# 6502__R8_EXP1.net
KiCad netlist of a schematic drawn in EAGLE
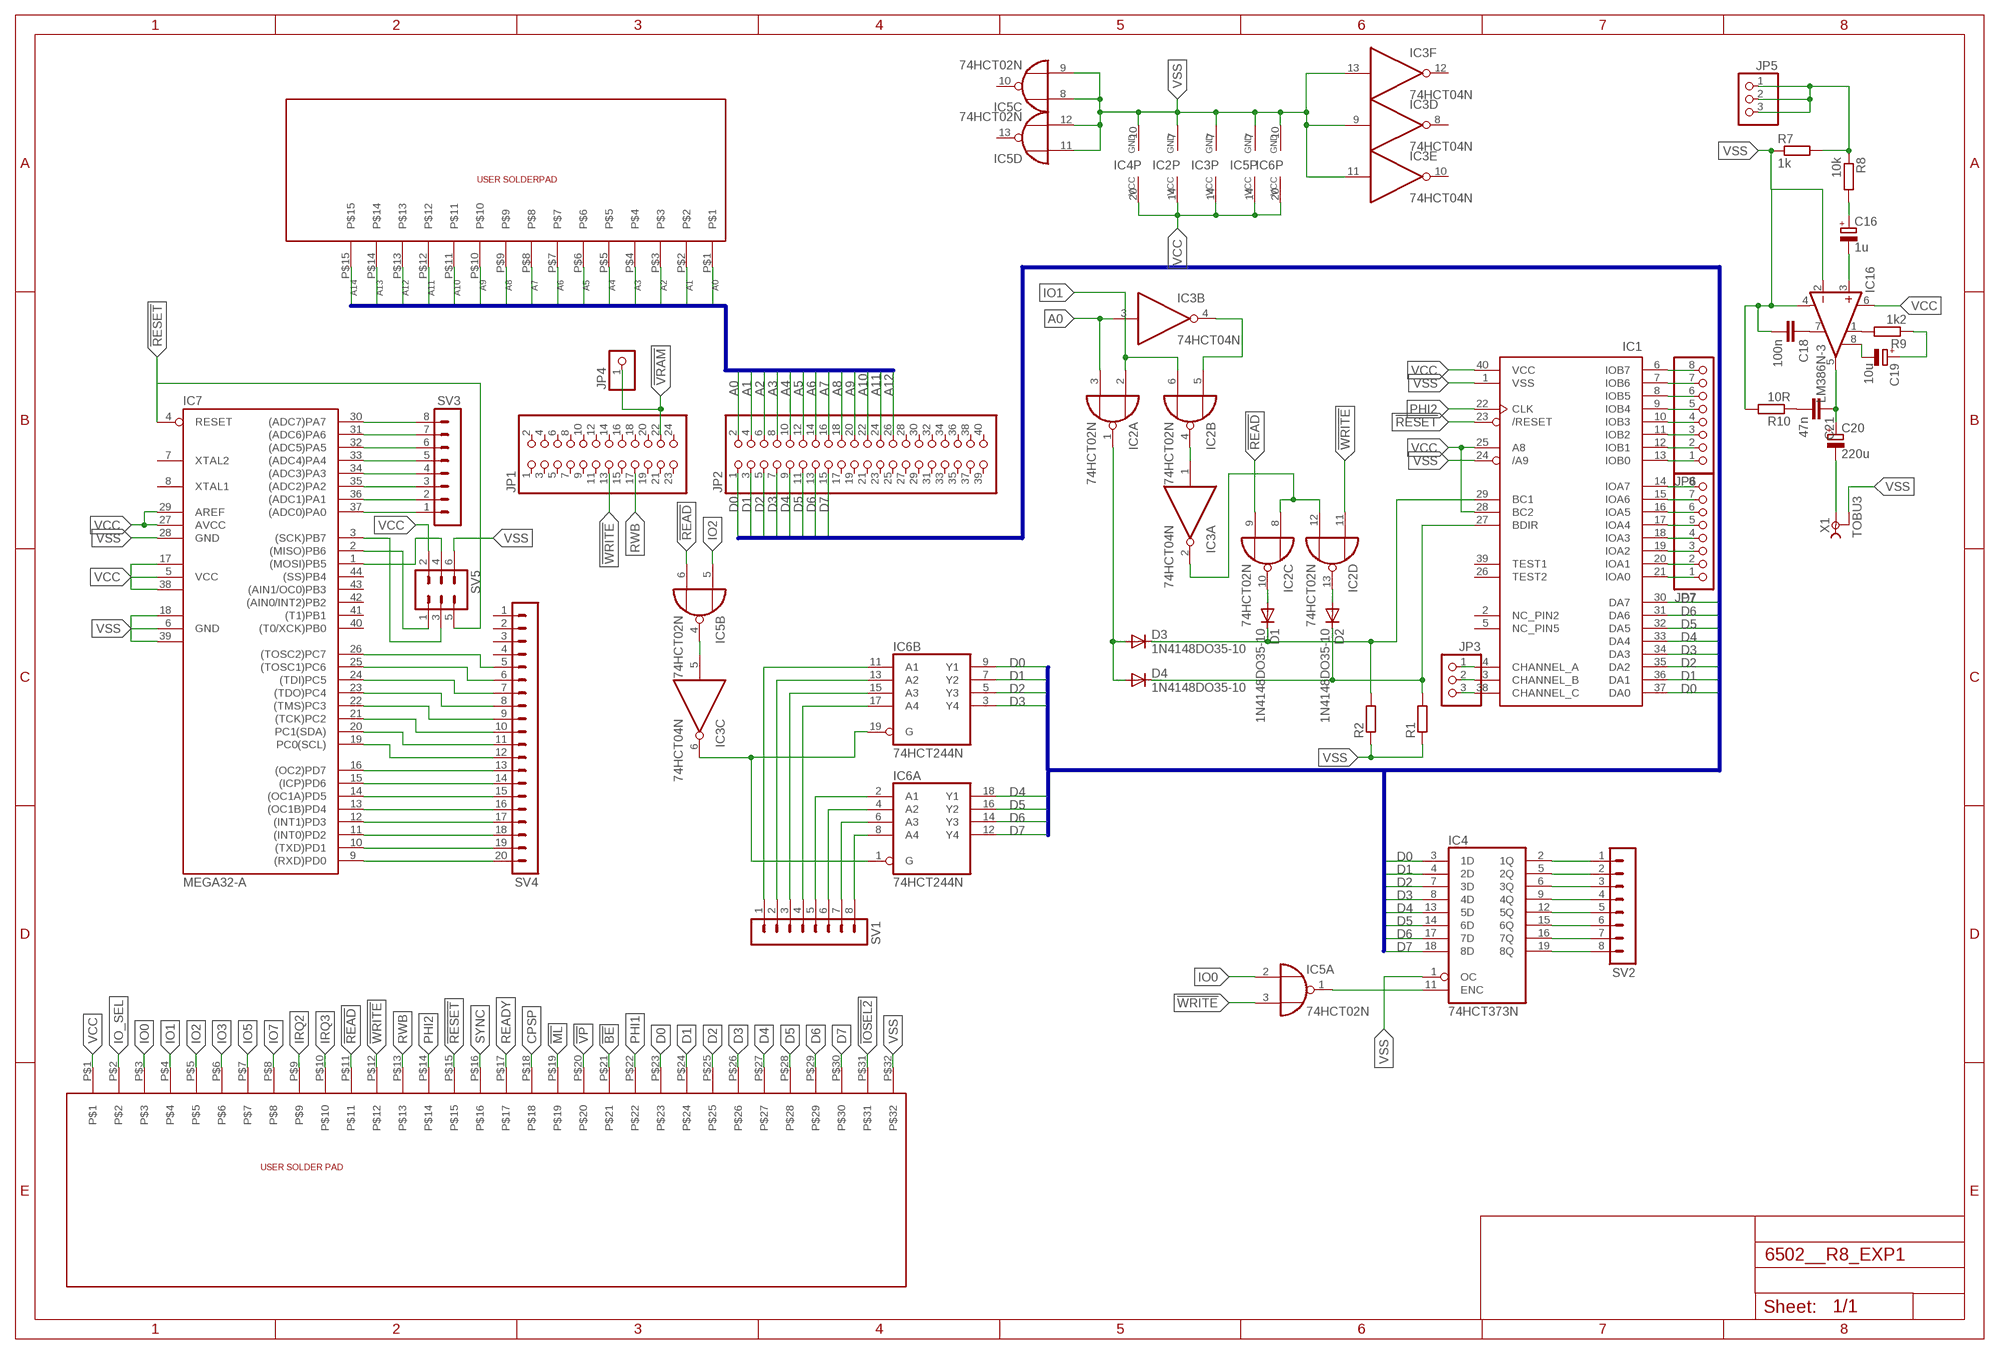
[diagram p0: schematic, sheet 1]

(export (version "E")
  (design (tool "Eeschema 10.0.6"))
  (components
    (comp (ref "C16")
      (value "1u")
      (footprint "eagle-import:E5-5")
      (libsource (lib "eagle-import") (part "CPOL-EUE5-5"))
    )
    (comp (ref "C18")
      (value "100n")
      (footprint "eagle-import:C025-030X050")
      (libsource (lib "eagle-import") (part "C-EU025-030X050"))
    )
    (comp (ref "C19")
      (value "10u")
      (footprint "eagle-import:E5-5")
      (libsource (lib "eagle-import") (part "CPOL-EUE5-5"))
    )
    (comp (ref "C20")
      (value "220u")
      (footprint "eagle-import:E5-5")
      (libsource (lib "eagle-import") (part "CPOL-EUE5-5"))
    )
    (comp (ref "C21")
      (value "47n")
      (footprint "eagle-import:C025-030X050")
      (libsource (lib "eagle-import") (part "C-EU025-030X050"))
    )
    (comp (ref "D1")
      (value "1N4148DO35-10")
      (footprint "eagle-import:DO35-10")
      (libsource (lib "eagle-import") (part "1N4148DO35-10"))
    )
    (comp (ref "D2")
      (value "1N4148DO35-10")
      (footprint "eagle-import:DO35-10")
      (libsource (lib "eagle-import") (part "1N4148DO35-10"))
    )
    (comp (ref "D3")
      (value "1N4148DO35-10")
      (footprint "eagle-import:DO35-10")
      (libsource (lib "eagle-import") (part "1N4148DO35-10"))
    )
    (comp (ref "D4")
      (value "1N4148DO35-10")
      (footprint "eagle-import:DO35-10")
      (libsource (lib "eagle-import") (part "1N4148DO35-10"))
    )
    (comp (ref "IC1")
      (value "AY-3-8910")
      (footprint "eagle-import:DIL40")
      (libsource (lib "eagle-import") (part "AY-3-8910"))
    )
    (comp (ref "IC2")
      (value "74HCT02N")
      (footprint "eagle-import:DIL14")
      (libsource (lib "eagle-import") (part "7402NHCT"))
    )
    (comp (ref "IC3")
      (value "74HCT04N")
      (footprint "eagle-import:DIL14")
      (libsource (lib "eagle-import") (part "7404NHCT"))
    )
    (comp (ref "IC4")
      (value "74HCT373N")
      (footprint "eagle-import:DIL20")
      (libsource (lib "eagle-import") (part "74373NHCT"))
    )
    (comp (ref "IC5")
      (value "74HCT02N")
      (footprint "eagle-import:DIL14")
      (libsource (lib "eagle-import") (part "7402NHCT"))
    )
    (comp (ref "IC6")
      (value "74HCT244N")
      (footprint "eagle-import:DIL20")
      (libsource (lib "eagle-import") (part "74244NHCT"))
    )
    (comp (ref "IC7")
      (value "MEGA32-A")
      (footprint "eagle-import:TQFP44")
      (fields (field (name "MPN") "ATMEGA32-16AU"))
      (libsource (lib "eagle-import") (part "MEGA32-A"))
    )
    (comp (ref "IC16")
      (value "LM386N-3")
      (footprint "eagle-import:DIL08")
      (libsource (lib "eagle-import") (part "LM386?-N3"))
    )
    (comp (ref "JP1")
      (value "PINHD-2X12")
      (footprint "eagle-import:2X12")
      (libsource (lib "eagle-import") (part "PINHD-2X12"))
    )
    (comp (ref "JP2")
      (value "PINHD-2X20")
      (footprint "eagle-import:2X20")
      (libsource (lib "eagle-import") (part "PINHD-2X20"))
    )
    (comp (ref "JP3")
      (value "PINHD-1X3")
      (footprint "eagle-import:1X03")
      (libsource (lib "eagle-import") (part "PINHD-1X3"))
    )
    (comp (ref "JP4")
      (value "PINHD-1X1")
      (footprint "eagle-import:1X01")
      (libsource (lib "eagle-import") (part "PINHD-1X1"))
    )
    (comp (ref "JP5")
      (value "PINHD-1X3")
      (footprint "eagle-import:1X03")
      (libsource (lib "eagle-import") (part "PINHD-1X3"))
    )
    (comp (ref "JP6")
      (value "PINHD-1X8")
      (footprint "eagle-import:1X08")
      (libsource (lib "eagle-import") (part "PINHD-1X8"))
    )
    (comp (ref "JP7")
      (value "PINHD-1X8")
      (footprint "eagle-import:1X08")
      (libsource (lib "eagle-import") (part "PINHD-1X8"))
    )
    (comp (ref "R1")
      (value "R-EU_0204/7")
      (footprint "eagle-import:0204_7")
      (libsource (lib "eagle-import") (part "R-EU_0204/7"))
    )
    (comp (ref "R2")
      (value "R-EU_0204/7")
      (footprint "eagle-import:0204_7")
      (libsource (lib "eagle-import") (part "R-EU_0204/7"))
    )
    (comp (ref "R7")
      (value "1k")
      (footprint "eagle-import:0207_12")
      (libsource (lib "eagle-import") (part "R-EU_0207/12"))
    )
    (comp (ref "R8")
      (value "10k")
      (footprint "eagle-import:0207_12")
      (libsource (lib "eagle-import") (part "R-EU_0207/12"))
    )
    (comp (ref "R9")
      (value "1k2")
      (footprint "eagle-import:0207_12")
      (libsource (lib "eagle-import") (part "R-EU_0207/12"))
    )
    (comp (ref "R10")
      (value "10R")
      (footprint "eagle-import:0207_12")
      (libsource (lib "eagle-import") (part "R-EU_0207/12"))
    )
    (comp (ref "SV1")
      (value "MA08-1")
      (footprint "eagle-import:MA08-1")
      (libsource (lib "eagle-import") (part "MA08-1"))
    )
    (comp (ref "SV2")
      (value "MA08-1")
      (footprint "eagle-import:MA08-1")
      (libsource (lib "eagle-import") (part "MA08-1"))
    )
    (comp (ref "SV3")
      (value "MA08-1")
      (footprint "eagle-import:MA08-1")
      (libsource (lib "eagle-import") (part "MA08-1"))
    )
    (comp (ref "SV4")
      (value "MA20-1")
      (footprint "eagle-import:MA20-1")
      (libsource (lib "eagle-import") (part "MA20-1"))
    )
    (comp (ref "SV5")
      (value "MA03-2")
      (footprint "eagle-import:MA03-2")
      (libsource (lib "eagle-import") (part "MA03-2"))
    )
    (comp (ref "U$2")
      (value "SOLDERPAD")
      (footprint "eagle-import:SOLDERPAD")
      (libsource (lib "eagle-import") (part "SOLDERPAD"))
    )
    (comp (ref "U$3")
      (value "SOLDERPAD2")
      (footprint "eagle-import:SOLDERPAD2")
      (libsource (lib "eagle-import") (part "SOLDERPAD2"))
    )
    (comp (ref "X1")
      (value "TOBU3")
      (footprint "eagle-import:TOBU3")
      (fields (field (name "MF") "FARNELL") (field (name "MPN") "TOBU 3"))
      (libsource (lib "eagle-import") (part "TOBU3"))
    )
  )
  (nets
    (net (code "1") (name "/A1") (class "Default")
      (node (ref "JP2") (pin "4") (pinfunction "4_4") (pintype "passive"))
      (node (ref "U$3") (pin "P$2") (pinfunction "P$2_P$2") (pintype "bidirectional"))
    )
    (net (code "2") (name "/A2") (class "Default")
      (node (ref "JP2") (pin "6") (pinfunction "6_6") (pintype "passive"))
      (node (ref "U$3") (pin "P$3") (pinfunction "P$3_P$3") (pintype "bidirectional"))
    )
    (net (code "3") (name "/A3") (class "Default")
      (node (ref "JP2") (pin "8") (pinfunction "8_8") (pintype "passive"))
      (node (ref "U$3") (pin "P$4") (pinfunction "P$4_P$4") (pintype "bidirectional"))
    )
    (net (code "4") (name "/A4") (class "Default")
      (node (ref "JP2") (pin "10") (pinfunction "10_10") (pintype "passive"))
      (node (ref "U$3") (pin "P$5") (pinfunction "P$5_P$5") (pintype "bidirectional"))
    )
    (net (code "5") (name "/A5") (class "Default")
      (node (ref "JP2") (pin "12") (pinfunction "12_12") (pintype "passive"))
      (node (ref "U$3") (pin "P$6") (pinfunction "P$6_P$6") (pintype "bidirectional"))
    )
    (net (code "6") (name "/A6") (class "Default")
      (node (ref "JP2") (pin "14") (pinfunction "14_14") (pintype "passive"))
      (node (ref "U$3") (pin "P$7") (pinfunction "P$7_P$7") (pintype "bidirectional"))
    )
    (net (code "7") (name "/A7") (class "Default")
      (node (ref "JP2") (pin "16") (pinfunction "16_16") (pintype "passive"))
      (node (ref "U$3") (pin "P$8") (pinfunction "P$8_P$8") (pintype "bidirectional"))
    )
    (net (code "8") (name "/A8") (class "Default")
      (node (ref "JP2") (pin "18") (pinfunction "18_18") (pintype "passive"))
      (node (ref "U$3") (pin "P$9") (pinfunction "P$9_P$9") (pintype "bidirectional"))
    )
    (net (code "9") (name "/A9") (class "Default")
      (node (ref "JP2") (pin "20") (pinfunction "20_20") (pintype "passive"))
      (node (ref "U$3") (pin "P$10") (pinfunction "P$10_P$10") (pintype "bidirectional"))
    )
    (net (code "10") (name "/A10") (class "Default")
      (node (ref "JP2") (pin "22") (pinfunction "22_22") (pintype "passive"))
      (node (ref "U$3") (pin "P$11") (pinfunction "P$11_P$11") (pintype "bidirectional"))
    )
    (net (code "11") (name "/A11") (class "Default")
      (node (ref "JP2") (pin "24") (pinfunction "24_24") (pintype "passive"))
      (node (ref "U$3") (pin "P$12") (pinfunction "P$12_P$12") (pintype "bidirectional"))
    )
    (net (code "12") (name "/A12") (class "Default")
      (node (ref "JP2") (pin "26") (pinfunction "26_26") (pintype "passive"))
      (node (ref "U$3") (pin "P$13") (pinfunction "P$13_P$13") (pintype "bidirectional"))
    )
    (net (code "13") (name "/A13") (class "Default")
      (node (ref "U$3") (pin "P$14") (pinfunction "P$14_P$14") (pintype "bidirectional"))
    )
    (net (code "14") (name "/A14") (class "Default")
      (node (ref "U$3") (pin "P$15") (pinfunction "P$15_P$15") (pintype "bidirectional"))
    )
    (net (code "15") (name "/~{BE}") (class "Default")
      (node (ref "U$2") (pin "P$21") (pinfunction "P$21_P$21") (pintype "bidirectional"))
    )
    (net (code "16") (name "/~{IOSEL2}") (class "Default")
      (node (ref "U$2") (pin "P$31") (pinfunction "P$31_P$31") (pintype "bidirectional"))
    )
    (net (code "17") (name "/~{ML}") (class "Default")
      (node (ref "U$2") (pin "P$19") (pinfunction "P$19_P$19") (pintype "bidirectional"))
    )
    (net (code "18") (name "/~{READ}") (class "Default")
      (node (ref "IC2") (pin "9") (pinfunction "I1_9") (pintype "input"))
      (node (ref "IC5") (pin "6") (pinfunction "I1_6") (pintype "input"))
      (node (ref "U$2") (pin "P$11") (pinfunction "P$11_P$11") (pintype "bidirectional"))
    )
    (net (code "19") (name "/~{RESET}") (class "Default")
      (node (ref "IC1") (pin "23") (pinfunction "/RESET_23") (pintype "input"))
      (node (ref "IC7") (pin "4") (pinfunction "RESET_4") (pintype "input"))
      (node (ref "SV5") (pin "5") (pinfunction "5_5") (pintype "passive"))
      (node (ref "U$2") (pin "P$15") (pinfunction "P$15_P$15") (pintype "bidirectional"))
    )
    (net (code "20") (name "/~{VP}") (class "Default")
      (node (ref "U$2") (pin "P$20") (pinfunction "P$20_P$20") (pintype "bidirectional"))
    )
    (net (code "21") (name "/~{VRAM}") (class "Default")
      (node (ref "JP1") (pin "22") (pinfunction "22_22") (pintype "passive"))
      (node (ref "JP4") (pin "1") (pinfunction "1_1") (pintype "passive"))
    )
    (net (code "22") (name "/~{WRITE}") (class "Default")
      (node (ref "IC2") (pin "11") (pinfunction "I0_11") (pintype "input"))
      (node (ref "IC5") (pin "3") (pinfunction "I1_3") (pintype "input"))
      (node (ref "JP1") (pin "13") (pinfunction "13_13") (pintype "passive"))
      (node (ref "U$2") (pin "P$12") (pinfunction "P$12_P$12") (pintype "bidirectional"))
    )
    (net (code "23") (name "A0") (class "Default")
      (node (ref "IC2") (pin "3") (pinfunction "I1_3") (pintype "input"))
      (node (ref "IC3") (pin "3") (pinfunction "I_3") (pintype "input"))
      (node (ref "JP2") (pin "2") (pinfunction "2_2") (pintype "passive"))
      (node (ref "U$3") (pin "P$1") (pinfunction "P$1_P$1") (pintype "bidirectional"))
    )
    (net (code "24") (name "CPSP") (class "Default")
      (node (ref "U$2") (pin "P$18") (pinfunction "P$18_P$18") (pintype "bidirectional"))
    )
    (net (code "25") (name "D0") (class "Default")
      (node (ref "IC1") (pin "37") (pinfunction "DA0_37") (pintype "bidirectional"))
      (node (ref "IC4") (pin "3") (pinfunction "1D_3") (pintype "input"))
      (node (ref "IC6") (pin "9") (pinfunction "Y1_9") (pintype "tri_state"))
      (node (ref "JP2") (pin "1") (pinfunction "1_1") (pintype "passive"))
      (node (ref "U$2") (pin "P$23") (pinfunction "P$23_P$23") (pintype "bidirectional"))
    )
    (net (code "26") (name "D1") (class "Default")
      (node (ref "IC1") (pin "36") (pinfunction "DA1_36") (pintype "bidirectional"))
      (node (ref "IC4") (pin "4") (pinfunction "2D_4") (pintype "input"))
      (node (ref "IC6") (pin "7") (pinfunction "Y2_7") (pintype "tri_state"))
      (node (ref "JP2") (pin "3") (pinfunction "3_3") (pintype "passive"))
      (node (ref "U$2") (pin "P$24") (pinfunction "P$24_P$24") (pintype "bidirectional"))
    )
    (net (code "27") (name "D2") (class "Default")
      (node (ref "IC1") (pin "35") (pinfunction "DA2_35") (pintype "bidirectional"))
      (node (ref "IC4") (pin "7") (pinfunction "3D_7") (pintype "input"))
      (node (ref "IC6") (pin "5") (pinfunction "Y3_5") (pintype "tri_state"))
      (node (ref "JP2") (pin "5") (pinfunction "5_5") (pintype "passive"))
      (node (ref "U$2") (pin "P$25") (pinfunction "P$25_P$25") (pintype "bidirectional"))
    )
    (net (code "28") (name "D3") (class "Default")
      (node (ref "IC1") (pin "34") (pinfunction "DA3_34") (pintype "bidirectional"))
      (node (ref "IC4") (pin "8") (pinfunction "4D_8") (pintype "input"))
      (node (ref "IC6") (pin "3") (pinfunction "Y4_3") (pintype "tri_state"))
      (node (ref "JP2") (pin "7") (pinfunction "7_7") (pintype "passive"))
      (node (ref "U$2") (pin "P$26") (pinfunction "P$26_P$26") (pintype "bidirectional"))
    )
    (net (code "29") (name "D4") (class "Default")
      (node (ref "IC1") (pin "33") (pinfunction "DA4_33") (pintype "bidirectional"))
      (node (ref "IC4") (pin "13") (pinfunction "5D_13") (pintype "input"))
      (node (ref "IC6") (pin "18") (pinfunction "Y1_18") (pintype "tri_state"))
      (node (ref "JP2") (pin "9") (pinfunction "9_9") (pintype "passive"))
      (node (ref "U$2") (pin "P$27") (pinfunction "P$27_P$27") (pintype "bidirectional"))
    )
    (net (code "30") (name "D5") (class "Default")
      (node (ref "IC1") (pin "32") (pinfunction "DA5_32") (pintype "bidirectional"))
      (node (ref "IC4") (pin "14") (pinfunction "6D_14") (pintype "input"))
      (node (ref "IC6") (pin "16") (pinfunction "Y2_16") (pintype "tri_state"))
      (node (ref "JP2") (pin "11") (pinfunction "11_11") (pintype "passive"))
      (node (ref "U$2") (pin "P$28") (pinfunction "P$28_P$28") (pintype "bidirectional"))
    )
    (net (code "31") (name "D6") (class "Default")
      (node (ref "IC1") (pin "31") (pinfunction "DA6_31") (pintype "bidirectional"))
      (node (ref "IC4") (pin "17") (pinfunction "7D_17") (pintype "input"))
      (node (ref "IC6") (pin "14") (pinfunction "Y3_14") (pintype "tri_state"))
      (node (ref "JP2") (pin "13") (pinfunction "13_13") (pintype "passive"))
      (node (ref "U$2") (pin "P$29") (pinfunction "P$29_P$29") (pintype "bidirectional"))
    )
    (net (code "32") (name "D7") (class "Default")
      (node (ref "IC1") (pin "30") (pinfunction "DA7_30") (pintype "bidirectional"))
      (node (ref "IC4") (pin "18") (pinfunction "8D_18") (pintype "input"))
      (node (ref "IC6") (pin "12") (pinfunction "Y4_12") (pintype "tri_state"))
      (node (ref "JP2") (pin "15") (pinfunction "15_15") (pintype "passive"))
      (node (ref "U$2") (pin "P$30") (pinfunction "P$30_P$30") (pintype "bidirectional"))
    )
    (net (code "33") (name "IO0") (class "Default")
      (node (ref "IC5") (pin "2") (pinfunction "I0_2") (pintype "input"))
      (node (ref "U$2") (pin "P$3") (pinfunction "P$3_P$3") (pintype "bidirectional"))
    )
    (net (code "34") (name "IO1") (class "Default")
      (node (ref "IC2") (pin "2") (pinfunction "I0_2") (pintype "input"))
      (node (ref "IC2") (pin "6") (pinfunction "I1_6") (pintype "input"))
      (node (ref "U$2") (pin "P$4") (pinfunction "P$4_P$4") (pintype "bidirectional"))
    )
    (net (code "35") (name "IO2") (class "Default")
      (node (ref "IC5") (pin "5") (pinfunction "I0_5") (pintype "input"))
      (node (ref "U$2") (pin "P$5") (pinfunction "P$5_P$5") (pintype "bidirectional"))
    )
    (net (code "36") (name "IO3") (class "Default")
      (node (ref "U$2") (pin "P$6") (pinfunction "P$6_P$6") (pintype "bidirectional"))
    )
    (net (code "37") (name "IO5") (class "Default")
      (node (ref "U$2") (pin "P$7") (pinfunction "P$7_P$7") (pintype "bidirectional"))
    )
    (net (code "38") (name "IO7") (class "Default")
      (node (ref "U$2") (pin "P$8") (pinfunction "P$8_P$8") (pintype "bidirectional"))
    )
    (net (code "39") (name "IO_SEL") (class "Default")
      (node (ref "U$2") (pin "P$2") (pinfunction "P$2_P$2") (pintype "bidirectional"))
    )
    (net (code "40") (name "IRQ2") (class "Default")
      (node (ref "U$2") (pin "P$9") (pinfunction "P$9_P$9") (pintype "bidirectional"))
    )
    (net (code "41") (name "IRQ3") (class "Default")
      (node (ref "U$2") (pin "P$10") (pinfunction "P$10_P$10") (pintype "bidirectional"))
    )
    (net (code "42") (name "Net-(C16-Pad+)") (class "Default")
      (node (ref "C16") (pin "+") (pinfunction "+_+") (pintype "passive"))
      (node (ref "R8") (pin "2") (pinfunction "2_2") (pintype "passive"))
    )
    (net (code "43") (name "Net-(C19-Pad+)") (class "Default")
      (node (ref "C19") (pin "+") (pinfunction "+_+") (pintype "passive"))
      (node (ref "R9") (pin "1") (pinfunction "1_1") (pintype "passive"))
    )
    (net (code "44") (name "Net-(C19-Pad-)") (class "Default")
      (node (ref "C19") (pin "-") (pinfunction "-_-") (pintype "passive"))
      (node (ref "IC16") (pin "8") (pinfunction "GAIN_8") (pintype "passive"))
    )
    (net (code "45") (name "Net-(C20-Pad-)") (class "Default")
      (node (ref "C20") (pin "-") (pinfunction "-_-") (pintype "passive"))
      (node (ref "X1") (pin "1") (pinfunction "1_1") (pintype "passive"))
    )
    (net (code "46") (name "Net-(C21-Pad2)") (class "Default")
      (node (ref "C21") (pin "2") (pinfunction "2_2") (pintype "passive"))
      (node (ref "R10") (pin "1") (pinfunction "1_1") (pintype "passive"))
    )
    (net (code "47") (name "Net-(IC1-BC1)") (class "Default")
      (node (ref "D1") (pin "C") (pinfunction "C_C") (pintype "passive"))
      (node (ref "D3") (pin "C") (pinfunction "C_C") (pintype "passive"))
      (node (ref "IC1") (pin "29") (pinfunction "BC1_29") (pintype "input"))
      (node (ref "R2") (pin "2") (pinfunction "2_2") (pintype "passive"))
    )
    (net (code "48") (name "Net-(IC1-BDIR)") (class "Default")
      (node (ref "D2") (pin "C") (pinfunction "C_C") (pintype "passive"))
      (node (ref "D4") (pin "C") (pinfunction "C_C") (pintype "passive"))
      (node (ref "IC1") (pin "27") (pinfunction "BDIR_27") (pintype "input"))
      (node (ref "R1") (pin "2") (pinfunction "2_2") (pintype "passive"))
    )
    (net (code "49") (name "Net-(IC1-CHANNEL_A)") (class "Default")
      (node (ref "IC1") (pin "4") (pinfunction "CHANNEL_A_4") (pintype "output"))
      (node (ref "JP3") (pin "1") (pinfunction "1_1") (pintype "passive"))
    )
    (net (code "50") (name "Net-(IC1-CHANNEL_B)") (class "Default")
      (node (ref "IC1") (pin "3") (pinfunction "CHANNEL_B_3") (pintype "output"))
      (node (ref "JP3") (pin "2") (pinfunction "2_2") (pintype "passive"))
    )
    (net (code "51") (name "Net-(IC1-CHANNEL_C)") (class "Default")
      (node (ref "IC1") (pin "38") (pinfunction "CHANNEL_C_38") (pintype "output"))
      (node (ref "JP3") (pin "3") (pinfunction "3_3") (pintype "passive"))
    )
    (net (code "52") (name "Net-(IC1-IOA0)") (class "Default")
      (node (ref "IC1") (pin "21") (pinfunction "IOA0_21") (pintype "bidirectional"))
      (node (ref "JP7") (pin "1") (pinfunction "1_1") (pintype "passive"))
    )
    (net (code "53") (name "Net-(IC1-IOA1)") (class "Default")
      (node (ref "IC1") (pin "20") (pinfunction "IOA1_20") (pintype "bidirectional"))
      (node (ref "JP7") (pin "2") (pinfunction "2_2") (pintype "passive"))
    )
    (net (code "54") (name "Net-(IC1-IOA2)") (class "Default")
      (node (ref "IC1") (pin "19") (pinfunction "IOA2_19") (pintype "bidirectional"))
      (node (ref "JP7") (pin "3") (pinfunction "3_3") (pintype "passive"))
    )
    (net (code "55") (name "Net-(IC1-IOA3)") (class "Default")
      (node (ref "IC1") (pin "18") (pinfunction "IOA3_18") (pintype "bidirectional"))
      (node (ref "JP7") (pin "4") (pinfunction "4_4") (pintype "passive"))
    )
    (net (code "56") (name "Net-(IC1-IOA4)") (class "Default")
      (node (ref "IC1") (pin "17") (pinfunction "IOA4_17") (pintype "bidirectional"))
      (node (ref "JP7") (pin "5") (pinfunction "5_5") (pintype "passive"))
    )
    (net (code "57") (name "Net-(IC1-IOA5)") (class "Default")
      (node (ref "IC1") (pin "16") (pinfunction "IOA5_16") (pintype "bidirectional"))
      (node (ref "JP7") (pin "6") (pinfunction "6_6") (pintype "passive"))
    )
    (net (code "58") (name "Net-(IC1-IOA6)") (class "Default")
      (node (ref "IC1") (pin "15") (pinfunction "IOA6_15") (pintype "bidirectional"))
      (node (ref "JP7") (pin "7") (pinfunction "7_7") (pintype "passive"))
    )
    (net (code "59") (name "Net-(IC1-IOA7)") (class "Default")
      (node (ref "IC1") (pin "14") (pinfunction "IOA7_14") (pintype "bidirectional"))
      (node (ref "JP7") (pin "8") (pinfunction "8_8") (pintype "passive"))
    )
    (net (code "60") (name "Net-(IC1-IOB0)") (class "Default")
      (node (ref "IC1") (pin "13") (pinfunction "IOB0_13") (pintype "bidirectional"))
      (node (ref "JP6") (pin "1") (pinfunction "1_1") (pintype "passive"))
    )
    (net (code "61") (name "Net-(IC1-IOB1)") (class "Default")
      (node (ref "IC1") (pin "12") (pinfunction "IOB1_12") (pintype "bidirectional"))
      (node (ref "JP6") (pin "2") (pinfunction "2_2") (pintype "passive"))
    )
    (net (code "62") (name "Net-(IC1-IOB2)") (class "Default")
      (node (ref "IC1") (pin "11") (pinfunction "IOB2_11") (pintype "bidirectional"))
      (node (ref "JP6") (pin "3") (pinfunction "3_3") (pintype "passive"))
    )
    (net (code "63") (name "Net-(IC1-IOB3)") (class "Default")
      (node (ref "IC1") (pin "10") (pinfunction "IOB3_10") (pintype "bidirectional"))
      (node (ref "JP6") (pin "4") (pinfunction "4_4") (pintype "passive"))
    )
    (net (code "64") (name "Net-(IC1-IOB4)") (class "Default")
      (node (ref "IC1") (pin "9") (pinfunction "IOB4_9") (pintype "bidirectional"))
      (node (ref "JP6") (pin "5") (pinfunction "5_5") (pintype "passive"))
    )
    (net (code "65") (name "Net-(IC1-IOB5)") (class "Default")
      (node (ref "IC1") (pin "8") (pinfunction "IOB5_8") (pintype "bidirectional"))
      (node (ref "JP6") (pin "6") (pinfunction "6_6") (pintype "passive"))
    )
    (net (code "66") (name "Net-(IC1-IOB6)") (class "Default")
      (node (ref "IC1") (pin "7") (pinfunction "IOB6_7") (pintype "bidirectional"))
      (node (ref "JP6") (pin "7") (pinfunction "7_7") (pintype "passive"))
    )
    (net (code "67") (name "Net-(IC1-IOB7)") (class "Default")
      (node (ref "IC1") (pin "6") (pinfunction "IOB7_6") (pintype "bidirectional"))
      (node (ref "JP6") (pin "8") (pinfunction "8_8") (pintype "passive"))
    )
    (net (code "68") (name "Net-(IC2A-O)") (class "Default")
      (node (ref "D3") (pin "A") (pinfunction "A_A") (pintype "passive"))
      (node (ref "D4") (pin "A") (pinfunction "A_A") (pintype "passive"))
      (node (ref "IC2") (pin "1") (pinfunction "O_1") (pintype "output"))
    )
    (net (code "69") (name "Net-(IC2B-I0)") (class "Default")
      (node (ref "IC2") (pin "5") (pinfunction "I0_5") (pintype "input"))
      (node (ref "IC3") (pin "4") (pinfunction "O_4") (pintype "output"))
    )
    (net (code "70") (name "Net-(IC2B-O)") (class "Default")
      (node (ref "IC2") (pin "4") (pinfunction "O_4") (pintype "output"))
      (node (ref "IC3") (pin "1") (pinfunction "I_1") (pintype "input"))
    )
    (net (code "71") (name "Net-(IC2C-I0)") (class "Default")
      (node (ref "IC2") (pin "12") (pinfunction "I1_12") (pintype "input"))
      (node (ref "IC2") (pin "8") (pinfunction "I0_8") (pintype "input"))
      (node (ref "IC3") (pin "2") (pinfunction "O_2") (pintype "output"))
    )
    (net (code "72") (name "Net-(IC2C-O)") (class "Default")
      (node (ref "D1") (pin "A") (pinfunction "A_A") (pintype "passive"))
      (node (ref "IC2") (pin "10") (pinfunction "O_10") (pintype "output"))
    )
    (net (code "73") (name "Net-(IC2D-O)") (class "Default")
      (node (ref "D2") (pin "A") (pinfunction "A_A") (pintype "passive"))
      (node (ref "IC2") (pin "13") (pinfunction "O_13") (pintype "output"))
    )
    (net (code "74") (name "Net-(IC3C-I)") (class "Default")
      (node (ref "IC3") (pin "5") (pinfunction "I_5") (pintype "input"))
      (node (ref "IC5") (pin "4") (pinfunction "O_4") (pintype "output"))
    )
    (net (code "75") (name "Net-(IC3C-O)") (class "Default")
      (node (ref "IC3") (pin "6") (pinfunction "O_6") (pintype "output"))
      (node (ref "IC6") (pin "1") (pinfunction "G_1") (pintype "input"))
      (node (ref "IC6") (pin "19") (pinfunction "G_19") (pintype "input"))
    )
    (net (code "76") (name "Net-(IC4A-1Q)") (class "Default")
      (node (ref "IC4") (pin "2") (pinfunction "1Q_2") (pintype "tri_state"))
      (node (ref "SV2") (pin "1") (pinfunction "1_1") (pintype "passive"))
    )
    (net (code "77") (name "Net-(IC4A-2Q)") (class "Default")
      (node (ref "IC4") (pin "5") (pinfunction "2Q_5") (pintype "tri_state"))
      (node (ref "SV2") (pin "2") (pinfunction "2_2") (pintype "passive"))
    )
    (net (code "78") (name "Net-(IC4A-3Q)") (class "Default")
      (node (ref "IC4") (pin "6") (pinfunction "3Q_6") (pintype "tri_state"))
      (node (ref "SV2") (pin "3") (pinfunction "3_3") (pintype "passive"))
    )
    (net (code "79") (name "Net-(IC4A-4Q)") (class "Default")
      (node (ref "IC4") (pin "9") (pinfunction "4Q_9") (pintype "tri_state"))
      (node (ref "SV2") (pin "4") (pinfunction "4_4") (pintype "passive"))
    )
    (net (code "80") (name "Net-(IC4A-5Q)") (class "Default")
      (node (ref "IC4") (pin "12") (pinfunction "5Q_12") (pintype "tri_state"))
      (node (ref "SV2") (pin "5") (pinfunction "5_5") (pintype "passive"))
    )
    (net (code "81") (name "Net-(IC4A-6Q)") (class "Default")
      (node (ref "IC4") (pin "15") (pinfunction "6Q_15") (pintype "tri_state"))
      (node (ref "SV2") (pin "6") (pinfunction "6_6") (pintype "passive"))
    )
    (net (code "82") (name "Net-(IC4A-7Q)") (class "Default")
      (node (ref "IC4") (pin "16") (pinfunction "7Q_16") (pintype "tri_state"))
      (node (ref "SV2") (pin "7") (pinfunction "7_7") (pintype "passive"))
    )
    (net (code "83") (name "Net-(IC4A-8Q)") (class "Default")
      (node (ref "IC4") (pin "19") (pinfunction "8Q_19") (pintype "tri_state"))
      (node (ref "SV2") (pin "8") (pinfunction "8_8") (pintype "passive"))
    )
    (net (code "84") (name "Net-(IC4A-ENC)") (class "Default")
      (node (ref "IC4") (pin "11") (pinfunction "ENC_11") (pintype "input"))
      (node (ref "IC5") (pin "1") (pinfunction "O_1") (pintype "output"))
    )
    (net (code "85") (name "Net-(IC6A-A1)") (class "Default")
      (node (ref "IC6") (pin "2") (pinfunction "A1_2") (pintype "input"))
      (node (ref "SV1") (pin "5") (pinfunction "5_5") (pintype "passive"))
    )
    (net (code "86") (name "Net-(IC6A-A2)") (class "Default")
      (node (ref "IC6") (pin "4") (pinfunction "A2_4") (pintype "input"))
      (node (ref "SV1") (pin "6") (pinfunction "6_6") (pintype "passive"))
    )
    (net (code "87") (name "Net-(IC6A-A3)") (class "Default")
      (node (ref "IC6") (pin "6") (pinfunction "A3_6") (pintype "input"))
      (node (ref "SV1") (pin "7") (pinfunction "7_7") (pintype "passive"))
    )
    (net (code "88") (name "Net-(IC6A-A4)") (class "Default")
      (node (ref "IC6") (pin "8") (pinfunction "A4_8") (pintype "input"))
      (node (ref "SV1") (pin "8") (pinfunction "8_8") (pintype "passive"))
    )
    (net (code "89") (name "Net-(IC6B-A1)") (class "Default")
      (node (ref "IC6") (pin "11") (pinfunction "A1_11") (pintype "input"))
      (node (ref "SV1") (pin "1") (pinfunction "1_1") (pintype "passive"))
    )
    (net (code "90") (name "Net-(IC6B-A2)") (class "Default")
      (node (ref "IC6") (pin "13") (pinfunction "A2_13") (pintype "input"))
      (node (ref "SV1") (pin "2") (pinfunction "2_2") (pintype "passive"))
    )
    (net (code "91") (name "Net-(IC6B-A3)") (class "Default")
      (node (ref "IC6") (pin "15") (pinfunction "A3_15") (pintype "input"))
      (node (ref "SV1") (pin "3") (pinfunction "3_3") (pintype "passive"))
    )
    (net (code "92") (name "Net-(IC6B-A4)") (class "Default")
      (node (ref "IC6") (pin "17") (pinfunction "A4_17") (pintype "input"))
      (node (ref "SV1") (pin "4") (pinfunction "4_4") (pintype "passive"))
    )
    (net (code "93") (name "Net-(IC7-(ADC0)PA0)") (class "Default")
      (node (ref "IC7") (pin "37") (pinfunction "(ADC0)PA0_37") (pintype "bidirectional"))
      (node (ref "SV3") (pin "1") (pinfunction "1_1") (pintype "passive"))
    )
    (net (code "94") (name "Net-(IC7-(ADC1)PA1)") (class "Default")
      (node (ref "IC7") (pin "36") (pinfunction "(ADC1)PA1_36") (pintype "bidirectional"))
      (node (ref "SV3") (pin "2") (pinfunction "2_2") (pintype "passive"))
    )
    (net (code "95") (name "Net-(IC7-(ADC2)PA2)") (class "Default")
      (node (ref "IC7") (pin "35") (pinfunction "(ADC2)PA2_35") (pintype "bidirectional"))
      (node (ref "SV3") (pin "3") (pinfunction "3_3") (pintype "passive"))
    )
    (net (code "96") (name "Net-(IC7-(ADC3)PA3)") (class "Default")
      (node (ref "IC7") (pin "34") (pinfunction "(ADC3)PA3_34") (pintype "bidirectional"))
      (node (ref "SV3") (pin "4") (pinfunction "4_4") (pintype "passive"))
    )
    (net (code "97") (name "Net-(IC7-(ADC4)PA4)") (class "Default")
      (node (ref "IC7") (pin "33") (pinfunction "(ADC4)PA4_33") (pintype "bidirectional"))
      (node (ref "SV3") (pin "5") (pinfunction "5_5") (pintype "passive"))
    )
    (net (code "98") (name "Net-(IC7-(ADC5)PA5)") (class "Default")
      (node (ref "IC7") (pin "32") (pinfunction "(ADC5)PA5_32") (pintype "bidirectional"))
      (node (ref "SV3") (pin "6") (pinfunction "6_6") (pintype "passive"))
    )
    (net (code "99") (name "Net-(IC7-(ADC6)PA6)") (class "Default")
      (node (ref "IC7") (pin "31") (pinfunction "(ADC6)PA6_31") (pintype "bidirectional"))
      (node (ref "SV3") (pin "7") (pinfunction "7_7") (pintype "passive"))
    )
    (net (code "100") (name "Net-(IC7-(ADC7)PA7)") (class "Default")
      (node (ref "IC7") (pin "30") (pinfunction "(ADC7)PA7_30") (pintype "bidirectional"))
      (node (ref "SV3") (pin "8") (pinfunction "8_8") (pintype "passive"))
    )
    (net (code "101") (name "Net-(IC7-(ICP)PD6)") (class "Default")
      (node (ref "IC7") (pin "15") (pinfunction "(ICP)PD6_15") (pintype "bidirectional"))
      (node (ref "SV4") (pin "14") (pinfunction "14_14") (pintype "passive"))
    )
    (net (code "102") (name "Net-(IC7-(INT0)PD2)") (class "Default")
      (node (ref "IC7") (pin "11") (pinfunction "(INT0)PD2_11") (pintype "bidirectional"))
      (node (ref "SV4") (pin "18") (pinfunction "18_18") (pintype "passive"))
    )
    (net (code "103") (name "Net-(IC7-(INT1)PD3)") (class "Default")
      (node (ref "IC7") (pin "12") (pinfunction "(INT1)PD3_12") (pintype "bidirectional"))
      (node (ref "SV4") (pin "17") (pinfunction "17_17") (pintype "passive"))
    )
    (net (code "104") (name "Net-(IC7-(MISO)PB6)") (class "Default")
      (node (ref "IC7") (pin "2") (pinfunction "(MISO)PB6_2") (pintype "bidirectional"))
      (node (ref "SV5") (pin "1") (pinfunction "1_1") (pintype "passive"))
    )
    (net (code "105") (name "Net-(IC7-(MOSI)PB5)") (class "Default")
      (node (ref "IC7") (pin "1") (pinfunction "(MOSI)PB5_1") (pintype "bidirectional"))
      (node (ref "SV5") (pin "4") (pinfunction "4_4") (pintype "passive"))
    )
    (net (code "106") (name "Net-(IC7-(OC1A)PD5)") (class "Default")
      (node (ref "IC7") (pin "14") (pinfunction "(OC1A)PD5_14") (pintype "bidirectional"))
      (node (ref "SV4") (pin "15") (pinfunction "15_15") (pintype "passive"))
    )
    (net (code "107") (name "Net-(IC7-(OC1B)PD4)") (class "Default")
      (node (ref "IC7") (pin "13") (pinfunction "(OC1B)PD4_13") (pintype "bidirectional"))
      (node (ref "SV4") (pin "16") (pinfunction "16_16") (pintype "passive"))
    )
    (net (code "108") (name "Net-(IC7-(OC2)PD7)") (class "Default")
      (node (ref "IC7") (pin "16") (pinfunction "(OC2)PD7_16") (pintype "bidirectional"))
      (node (ref "SV4") (pin "13") (pinfunction "13_13") (pintype "passive"))
    )
    (net (code "109") (name "Net-(IC7-(RXD)PD0)") (class "Default")
      (node (ref "IC7") (pin "9") (pinfunction "(RXD)PD0_9") (pintype "bidirectional"))
      (node (ref "SV4") (pin "20") (pinfunction "20_20") (pintype "passive"))
    )
    (net (code "110") (name "Net-(IC7-(SCK)PB7)") (class "Default")
      (node (ref "IC7") (pin "3") (pinfunction "(SCK)PB7_3") (pintype "bidirectional"))
      (node (ref "SV5") (pin "3") (pinfunction "3_3") (pintype "passive"))
    )
    (net (code "111") (name "Net-(IC7-(TCK)PC2)") (class "Default")
      (node (ref "IC7") (pin "21") (pinfunction "(TCK)PC2_21") (pintype "bidirectional"))
      (node (ref "SV4") (pin "10") (pinfunction "10_10") (pintype "passive"))
    )
    (net (code "112") (name "Net-(IC7-(TDI)PC5)") (class "Default")
      (node (ref "IC7") (pin "24") (pinfunction "(TDI)PC5_24") (pintype "bidirectional"))
      (node (ref "SV4") (pin "7") (pinfunction "7_7") (pintype "passive"))
    )
    (net (code "113") (name "Net-(IC7-(TDO)PC4)") (class "Default")
      (node (ref "IC7") (pin "23") (pinfunction "(TDO)PC4_23") (pintype "bidirectional"))
      (node (ref "SV4") (pin "8") (pinfunction "8_8") (pintype "passive"))
    )
    (net (code "114") (name "Net-(IC7-(TMS)PC3)") (class "Default")
      (node (ref "IC7") (pin "22") (pinfunction "(TMS)PC3_22") (pintype "bidirectional"))
      (node (ref "SV4") (pin "9") (pinfunction "9_9") (pintype "passive"))
    )
    (net (code "115") (name "Net-(IC7-(TOSC1)PC6)") (class "Default")
      (node (ref "IC7") (pin "25") (pinfunction "(TOSC1)PC6_25") (pintype "bidirectional"))
      (node (ref "SV4") (pin "6") (pinfunction "6_6") (pintype "passive"))
    )
    (net (code "116") (name "Net-(IC7-(TOSC2)PC7)") (class "Default")
      (node (ref "IC7") (pin "26") (pinfunction "(TOSC2)PC7_26") (pintype "bidirectional"))
      (node (ref "SV4") (pin "5") (pinfunction "5_5") (pintype "passive"))
    )
    (net (code "117") (name "Net-(IC7-(TXD)PD1)") (class "Default")
      (node (ref "IC7") (pin "10") (pinfunction "(TXD)PD1_10") (pintype "bidirectional"))
      (node (ref "SV4") (pin "19") (pinfunction "19_19") (pintype "passive"))
    )
    (net (code "118") (name "Net-(IC7-PC0(SCL))") (class "Default")
      (node (ref "IC7") (pin "19") (pinfunction "PC0(SCL)_19") (pintype "bidirectional"))
      (node (ref "SV4") (pin "12") (pinfunction "12_12") (pintype "passive"))
    )
    (net (code "119") (name "Net-(IC7-PC1(SDA))") (class "Default")
      (node (ref "IC7") (pin "20") (pinfunction "PC1(SDA)_20") (pintype "bidirectional"))
      (node (ref "SV4") (pin "11") (pinfunction "11_11") (pintype "passive"))
    )
    (net (code "120") (name "Net-(IC16-+IN)") (class "Default")
      (node (ref "C16") (pin "-") (pinfunction "-_-") (pintype "passive"))
      (node (ref "IC16") (pin "3") (pinfunction "+IN_3") (pintype "input"))
    )
    (net (code "121") (name "Net-(IC16-BYPASS)") (class "Default")
      (node (ref "C18") (pin "1") (pinfunction "1_1") (pintype "passive"))
      (node (ref "IC16") (pin "7") (pinfunction "BYPASS_7") (pintype "passive"))
    )
    (net (code "122") (name "Net-(IC16-GAIN-Pad1)") (class "Default")
      (node (ref "IC16") (pin "1") (pinfunction "GAIN_1") (pintype "passive"))
      (node (ref "R9") (pin "2") (pinfunction "2_2") (pintype "passive"))
    )
    (net (code "123") (name "Net-(IC16-OUT)") (class "Default")
      (node (ref "C20") (pin "+") (pinfunction "+_+") (pintype "passive"))
      (node (ref "C21") (pin "1") (pinfunction "1_1") (pintype "passive"))
      (node (ref "IC16") (pin "5") (pinfunction "OUT_5") (pintype "output"))
    )
    (net (code "124") (name "Net-(JP5-Pad1)") (class "Default")
      (node (ref "JP5") (pin "1") (pinfunction "1_1") (pintype "passive"))
      (node (ref "JP5") (pin "2") (pinfunction "2_2") (pintype "passive"))
      (node (ref "JP5") (pin "3") (pinfunction "3_3") (pintype "passive"))
      (node (ref "R7") (pin "2") (pinfunction "2_2") (pintype "passive"))
      (node (ref "R8") (pin "1") (pinfunction "1_1") (pintype "passive"))
    )
    (net (code "125") (name "PHI1") (class "Default")
      (node (ref "U$2") (pin "P$22") (pinfunction "P$22_P$22") (pintype "bidirectional"))
    )
    (net (code "126") (name "PHI2") (class "Default")
      (node (ref "IC1") (pin "22") (pinfunction "CLK_22") (pintype "input"))
      (node (ref "U$2") (pin "P$14") (pinfunction "P$14_P$14") (pintype "bidirectional"))
    )
    (net (code "127") (name "READY") (class "Default")
      (node (ref "U$2") (pin "P$17") (pinfunction "P$17_P$17") (pintype "bidirectional"))
    )
    (net (code "128") (name "RWB") (class "Default")
      (node (ref "JP1") (pin "17") (pinfunction "17_17") (pintype "passive"))
      (node (ref "U$2") (pin "P$13") (pinfunction "P$13_P$13") (pintype "bidirectional"))
    )
    (net (code "129") (name "SYNC") (class "Default")
      (node (ref "U$2") (pin "P$16") (pinfunction "P$16_P$16") (pintype "bidirectional"))
    )
    (net (code "130") (name "VCC") (class "Default")
      (node (ref "IC1") (pin "25") (pinfunction "A8_25") (pintype "bidirectional"))
      (node (ref "IC1") (pin "28") (pinfunction "BC2_28") (pintype "input"))
      (node (ref "IC1") (pin "40") (pinfunction "VCC_40") (pintype "power_in"))
      (node (ref "IC16") (pin "6") (pinfunction "VS_6") (pintype "power_in"))
      (node (ref "IC2") (pin "14") (pinfunction "VCC_14") (pintype "power_in"))
      (node (ref "IC3") (pin "14") (pinfunction "VCC_14") (pintype "power_in"))
      (node (ref "IC4") (pin "20") (pinfunction "VCC_20") (pintype "power_in"))
      (node (ref "IC5") (pin "14") (pinfunction "VCC_14") (pintype "power_in"))
      (node (ref "IC6") (pin "20") (pinfunction "VCC_20") (pintype "power_in"))
      (node (ref "IC7") (pin "17") (pinfunction "VCC1_17") (pintype "power_in"))
      (node (ref "IC7") (pin "27") (pinfunction "AVCC_27") (pintype "power_in"))
      (node (ref "IC7") (pin "29") (pinfunction "AREF_29") (pintype "passive"))
      (node (ref "IC7") (pin "38") (pinfunction "VCC2_38") (pintype "power_in"))
      (node (ref "IC7") (pin "5") (pinfunction "VCC_5") (pintype "power_in"))
      (node (ref "SV5") (pin "2") (pinfunction "2_2") (pintype "passive"))
      (node (ref "U$2") (pin "P$1") (pinfunction "P$1_P$1") (pintype "bidirectional"))
    )
    (net (code "131") (name "VSS") (class "Default")
      (node (ref "C18") (pin "2") (pinfunction "2_2") (pintype "passive"))
      (node (ref "IC1") (pin "1") (pinfunction "VSS_1") (pintype "power_in"))
      (node (ref "IC1") (pin "24") (pinfunction "/A9_24") (pintype "bidirectional"))
      (node (ref "IC16") (pin "2") (pinfunction "-IN_2") (pintype "input"))
      (node (ref "IC16") (pin "4") (pinfunction "GND_4") (pintype "power_in"))
      (node (ref "IC2") (pin "7") (pinfunction "GND_7") (pintype "power_in"))
      (node (ref "IC3") (pin "11") (pinfunction "I_11") (pintype "input"))
      (node (ref "IC3") (pin "13") (pinfunction "I_13") (pintype "input"))
      (node (ref "IC3") (pin "7") (pinfunction "GND_7") (pintype "power_in"))
      (node (ref "IC3") (pin "9") (pinfunction "I_9") (pintype "input"))
      (node (ref "IC4") (pin "1") (pinfunction "OC_1") (pintype "input"))
      (node (ref "IC4") (pin "10") (pinfunction "GND_10") (pintype "power_in"))
      (node (ref "IC5") (pin "11") (pinfunction "I0_11") (pintype "input"))
      (node (ref "IC5") (pin "12") (pinfunction "I1_12") (pintype "input"))
      (node (ref "IC5") (pin "7") (pinfunction "GND_7") (pintype "power_in"))
      (node (ref "IC5") (pin "8") (pinfunction "I0_8") (pintype "input"))
      (node (ref "IC5") (pin "9") (pinfunction "I1_9") (pintype "input"))
      (node (ref "IC6") (pin "10") (pinfunction "GND_10") (pintype "power_in"))
      (node (ref "IC7") (pin "18") (pinfunction "GND1_18") (pintype "power_in"))
      (node (ref "IC7") (pin "28") (pinfunction "GND_28") (pintype "power_in"))
      (node (ref "IC7") (pin "39") (pinfunction "GND2_39") (pintype "power_in"))
      (node (ref "IC7") (pin "6") (pinfunction "GND_6") (pintype "power_in"))
      (node (ref "R1") (pin "1") (pinfunction "1_1") (pintype "passive"))
      (node (ref "R10") (pin "2") (pinfunction "2_2") (pintype "passive"))
      (node (ref "R2") (pin "1") (pinfunction "1_1") (pintype "passive"))
      (node (ref "R7") (pin "1") (pinfunction "1_1") (pintype "passive"))
      (node (ref "SV5") (pin "6") (pinfunction "6_6") (pintype "passive"))
      (node (ref "U$2") (pin "P$32") (pinfunction "P$32_P$32") (pintype "bidirectional"))
      (node (ref "X1") (pin "2") (pinfunction "2_2") (pintype "passive"))
      (node (ref "X1") (pin "2@1") (pinfunction "2_2@1") (pintype "passive"))
      (node (ref "X1") (pin "2@2") (pinfunction "2_2@2") (pintype "passive"))
    )
    (net (code "132") (name "unconnected-(IC1-NC_PIN2-Pad2)") (class "Default")
      (node (ref "IC1") (pin "2") (pinfunction "NC_PIN2_2") (pintype "no_connect"))
    )
    (net (code "133") (name "unconnected-(IC1-NC_PIN5-Pad5)") (class "Default")
      (node (ref "IC1") (pin "5") (pinfunction "NC_PIN5_5") (pintype "bidirectional"))
    )
    (net (code "134") (name "unconnected-(IC1-TEST1-Pad39)") (class "Default")
      (node (ref "IC1") (pin "39") (pinfunction "TEST1_39") (pintype "no_connect"))
    )
    (net (code "135") (name "unconnected-(IC1-TEST2-Pad26)") (class "Default")
      (node (ref "IC1") (pin "26") (pinfunction "TEST2_26") (pintype "no_connect"))
    )
    (net (code "136") (name "unconnected-(IC3D-O-Pad8)") (class "Default")
      (node (ref "IC3") (pin "8") (pinfunction "O_8") (pintype "output"))
    )
    (net (code "137") (name "unconnected-(IC3E-O-Pad10)") (class "Default")
      (node (ref "IC3") (pin "10") (pinfunction "O_10") (pintype "output"))
    )
    (net (code "138") (name "unconnected-(IC3F-O-Pad12)") (class "Default")
      (node (ref "IC3") (pin "12") (pinfunction "O_12") (pintype "output"))
    )
    (net (code "139") (name "unconnected-(IC5C-O-Pad10)") (class "Default")
      (node (ref "IC5") (pin "10") (pinfunction "O_10") (pintype "output"))
    )
    (net (code "140") (name "unconnected-(IC5D-O-Pad13)") (class "Default")
      (node (ref "IC5") (pin "13") (pinfunction "O_13") (pintype "output"))
    )
    (net (code "141") (name "unconnected-(IC7-(AIN0{slash}INT2)PB2-Pad42)") (class "Default")
      (node (ref "IC7") (pin "42") (pinfunction "(AIN0/INT2)PB2_42") (pintype "bidirectional"))
    )
    (net (code "142") (name "unconnected-(IC7-(AIN1{slash}OC0)PB3-Pad43)") (class "Default")
      (node (ref "IC7") (pin "43") (pinfunction "(AIN1/OC0)PB3_43") (pintype "bidirectional"))
    )
    (net (code "143") (name "unconnected-(IC7-(SS)PB4-Pad44)") (class "Default")
      (node (ref "IC7") (pin "44") (pinfunction "(SS)PB4_44") (pintype "bidirectional"))
    )
    (net (code "144") (name "unconnected-(IC7-(T0{slash}XCK)PB0-Pad40)") (class "Default")
      (node (ref "IC7") (pin "40") (pinfunction "(T0/XCK)PB0_40") (pintype "bidirectional"))
    )
    (net (code "145") (name "unconnected-(IC7-(T1)PB1-Pad41)") (class "Default")
      (node (ref "IC7") (pin "41") (pinfunction "(T1)PB1_41") (pintype "bidirectional"))
    )
    (net (code "146") (name "unconnected-(IC7-XTAL1-Pad8)") (class "Default")
      (node (ref "IC7") (pin "8") (pinfunction "XTAL1_8") (pintype "bidirectional"))
    )
    (net (code "147") (name "unconnected-(IC7-XTAL2-Pad7)") (class "Default")
      (node (ref "IC7") (pin "7") (pinfunction "XTAL2_7") (pintype "bidirectional"))
    )
    (net (code "148") (name "unconnected-(JP1-Pad1)") (class "Default")
      (node (ref "JP1") (pin "1") (pinfunction "1_1") (pintype "passive"))
    )
    (net (code "149") (name "unconnected-(JP1-Pad2)") (class "Default")
      (node (ref "JP1") (pin "2") (pinfunction "2_2") (pintype "passive"))
    )
    (net (code "150") (name "unconnected-(JP1-Pad3)") (class "Default")
      (node (ref "JP1") (pin "3") (pinfunction "3_3") (pintype "passive"))
    )
    (net (code "151") (name "unconnected-(JP1-Pad4)") (class "Default")
      (node (ref "JP1") (pin "4") (pinfunction "4_4") (pintype "passive"))
    )
    (net (code "152") (name "unconnected-(JP1-Pad5)") (class "Default")
      (node (ref "JP1") (pin "5") (pinfunction "5_5") (pintype "passive"))
    )
    (net (code "153") (name "unconnected-(JP1-Pad6)") (class "Default")
      (node (ref "JP1") (pin "6") (pinfunction "6_6") (pintype "passive"))
    )
    (net (code "154") (name "unconnected-(JP1-Pad7)") (class "Default")
      (node (ref "JP1") (pin "7") (pinfunction "7_7") (pintype "passive"))
    )
    (net (code "155") (name "unconnected-(JP1-Pad8)") (class "Default")
      (node (ref "JP1") (pin "8") (pinfunction "8_8") (pintype "passive"))
    )
    (net (code "156") (name "unconnected-(JP1-Pad9)") (class "Default")
      (node (ref "JP1") (pin "9") (pinfunction "9_9") (pintype "passive"))
    )
    (net (code "157") (name "unconnected-(JP1-Pad10)") (class "Default")
      (node (ref "JP1") (pin "10") (pinfunction "10_10") (pintype "passive"))
    )
    (net (code "158") (name "unconnected-(JP1-Pad11)") (class "Default")
      (node (ref "JP1") (pin "11") (pinfunction "11_11") (pintype "passive"))
    )
    (net (code "159") (name "unconnected-(JP1-Pad12)") (class "Default")
      (node (ref "JP1") (pin "12") (pinfunction "12_12") (pintype "passive"))
    )
    (net (code "160") (name "unconnected-(JP1-Pad14)") (class "Default")
      (node (ref "JP1") (pin "14") (pinfunction "14_14") (pintype "passive"))
    )
    (net (code "161") (name "unconnected-(JP1-Pad15)") (class "Default")
      (node (ref "JP1") (pin "15") (pinfunction "15_15") (pintype "passive"))
    )
    (net (code "162") (name "unconnected-(JP1-Pad16)") (class "Default")
      (node (ref "JP1") (pin "16") (pinfunction "16_16") (pintype "passive"))
    )
    (net (code "163") (name "unconnected-(JP1-Pad18)") (class "Default")
      (node (ref "JP1") (pin "18") (pinfunction "18_18") (pintype "passive"))
    )
    (net (code "164") (name "unconnected-(JP1-Pad19)") (class "Default")
      (node (ref "JP1") (pin "19") (pinfunction "19_19") (pintype "passive"))
    )
    (net (code "165") (name "unconnected-(JP1-Pad20)") (class "Default")
      (node (ref "JP1") (pin "20") (pinfunction "20_20") (pintype "passive"))
    )
    (net (code "166") (name "unconnected-(JP1-Pad21)") (class "Default")
      (node (ref "JP1") (pin "21") (pinfunction "21_21") (pintype "passive"))
    )
    (net (code "167") (name "unconnected-(JP1-Pad23)") (class "Default")
      (node (ref "JP1") (pin "23") (pinfunction "23_23") (pintype "passive"))
    )
    (net (code "168") (name "unconnected-(JP1-Pad24)") (class "Default")
      (node (ref "JP1") (pin "24") (pinfunction "24_24") (pintype "passive"))
    )
    (net (code "169") (name "unconnected-(JP2-Pad17)") (class "Default")
      (node (ref "JP2") (pin "17") (pinfunction "17_17") (pintype "passive"))
    )
    (net (code "170") (name "unconnected-(JP2-Pad19)") (class "Default")
      (node (ref "JP2") (pin "19") (pinfunction "19_19") (pintype "passive"))
    )
    (net (code "171") (name "unconnected-(JP2-Pad21)") (class "Default")
      (node (ref "JP2") (pin "21") (pinfunction "21_21") (pintype "passive"))
    )
    (net (code "172") (name "unconnected-(JP2-Pad23)") (class "Default")
      (node (ref "JP2") (pin "23") (pinfunction "23_23") (pintype "passive"))
    )
    (net (code "173") (name "unconnected-(JP2-Pad25)") (class "Default")
      (node (ref "JP2") (pin "25") (pinfunction "25_25") (pintype "passive"))
    )
    (net (code "174") (name "unconnected-(JP2-Pad27)") (class "Default")
      (node (ref "JP2") (pin "27") (pinfunction "27_27") (pintype "passive"))
    )
    (net (code "175") (name "unconnected-(JP2-Pad28)") (class "Default")
      (node (ref "JP2") (pin "28") (pinfunction "28_28") (pintype "passive"))
    )
    (net (code "176") (name "unconnected-(JP2-Pad29)") (class "Default")
      (node (ref "JP2") (pin "29") (pinfunction "29_29") (pintype "passive"))
    )
    (net (code "177") (name "unconnected-(JP2-Pad30)") (class "Default")
      (node (ref "JP2") (pin "30") (pinfunction "30_30") (pintype "passive"))
    )
    (net (code "178") (name "unconnected-(JP2-Pad31)") (class "Default")
      (node (ref "JP2") (pin "31") (pinfunction "31_31") (pintype "passive"))
    )
    (net (code "179") (name "unconnected-(JP2-Pad32)") (class "Default")
      (node (ref "JP2") (pin "32") (pinfunction "32_32") (pintype "passive"))
    )
    (net (code "180") (name "unconnected-(JP2-Pad33)") (class "Default")
      (node (ref "JP2") (pin "33") (pinfunction "33_33") (pintype "passive"))
    )
    (net (code "181") (name "unconnected-(JP2-Pad34)") (class "Default")
      (node (ref "JP2") (pin "34") (pinfunction "34_34") (pintype "passive"))
    )
    (net (code "182") (name "unconnected-(JP2-Pad35)") (class "Default")
      (node (ref "JP2") (pin "35") (pinfunction "35_35") (pintype "passive"))
    )
    (net (code "183") (name "unconnected-(JP2-Pad36)") (class "Default")
      (node (ref "JP2") (pin "36") (pinfunction "36_36") (pintype "passive"))
    )
    (net (code "184") (name "unconnected-(JP2-Pad37)") (class "Default")
      (node (ref "JP2") (pin "37") (pinfunction "37_37") (pintype "passive"))
    )
    (net (code "185") (name "unconnected-(JP2-Pad38)") (class "Default")
      (node (ref "JP2") (pin "38") (pinfunction "38_38") (pintype "passive"))
    )
    (net (code "186") (name "unconnected-(JP2-Pad39)") (class "Default")
      (node (ref "JP2") (pin "39") (pinfunction "39_39") (pintype "passive"))
    )
    (net (code "187") (name "unconnected-(JP2-Pad40)") (class "Default")
      (node (ref "JP2") (pin "40") (pinfunction "40_40") (pintype "passive"))
    )
    (net (code "188") (name "unconnected-(SV4-Pad1)") (class "Default")
      (node (ref "SV4") (pin "1") (pinfunction "1_1") (pintype "passive"))
    )
    (net (code "189") (name "unconnected-(SV4-Pad2)") (class "Default")
      (node (ref "SV4") (pin "2") (pinfunction "2_2") (pintype "passive"))
    )
    (net (code "190") (name "unconnected-(SV4-Pad3)") (class "Default")
      (node (ref "SV4") (pin "3") (pinfunction "3_3") (pintype "passive"))
    )
    (net (code "191") (name "unconnected-(SV4-Pad4)") (class "Default")
      (node (ref "SV4") (pin "4") (pinfunction "4_4") (pintype "passive"))
    )
  )
)
